# OECOC_controlbord.net
KiCad netlist of a schematic drawn in EAGLE
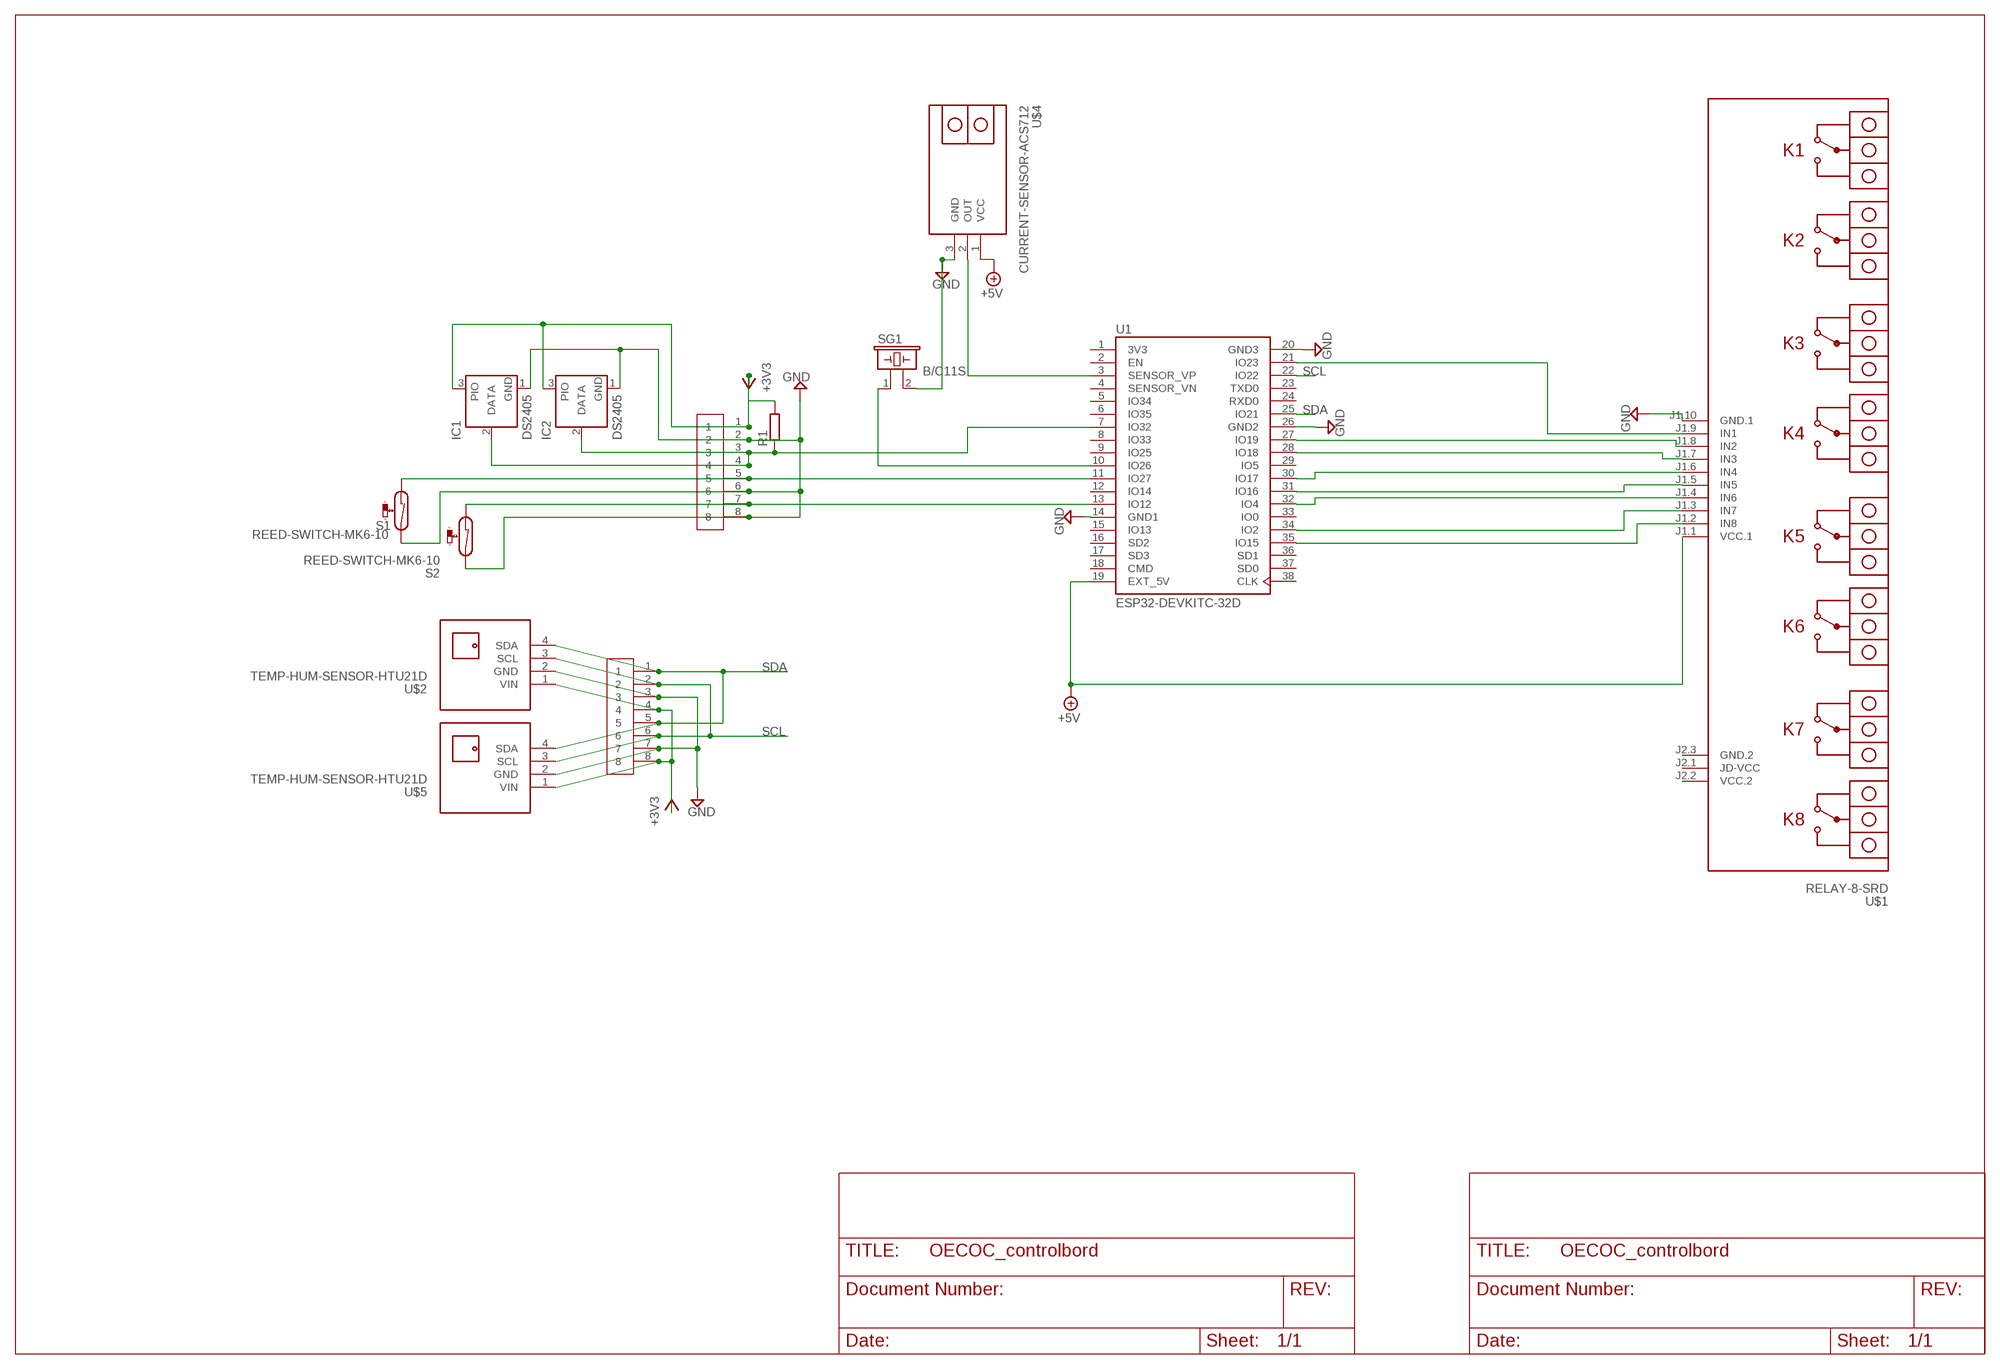
[diagram p0: schematic, sheet 1]

(export (version "E")
  (design (tool "Eeschema 10.0.6"))
  (components
    (comp (ref "IC1")
      (value "DS2405")
      (footprint "eagle-import:TO92-")
      (fields (field (name "MF") "DALLAS SEMICONDUCTOR"))
      (libsource (lib "eagle-import") (part "DS2405"))
    )
    (comp (ref "IC2")
      (value "DS2405")
      (footprint "eagle-import:TO92-")
      (fields (field (name "MF") "DALLAS SEMICONDUCTOR"))
      (libsource (lib "eagle-import") (part "DS2405"))
    )
    (comp (ref "R1")
      (value "R-EU_0207/10")
      (footprint "eagle-import:0207_10")
      (libsource (lib "eagle-import") (part "R-EU_0207/10"))
    )
    (comp (ref "S1")
      (value "REED-SWITCH-MK6-10")
      (footprint "eagle-import:MK6-10")
      (libsource (lib "eagle-import") (part "REED-SWITCH-MK6-10"))
    )
    (comp (ref "S2")
      (value "REED-SWITCH-MK6-10")
      (footprint "eagle-import:MK6-10")
      (libsource (lib "eagle-import") (part "REED-SWITCH-MK6-10"))
    )
    (comp (ref "SG1")
      (value "B/C11S")
      (footprint "eagle-import:B_C11S")
      (libsource (lib "eagle-import") (part "B/C11S"))
    )
    (comp (ref "U$1")
      (value "RELAY-8-SRD")
      (footprint "eagle-import:RELAY-8-SRD")
      (libsource (lib "eagle-import") (part "RELAY-8-SRD"))
    )
    (comp (ref "U$2")
      (value "TEMP-HUM-SENSOR-HTU21D")
      (footprint "eagle-import:TEMP-HUM-SENSOR-HTU21D")
      (libsource (lib "eagle-import") (part "TEMP-HUM-SENSOR-HTU21D"))
    )
    (comp (ref "U$3")
      (value "PHOENIXCONTACT_PINSTRIP")
      (footprint "eagle-import:HDRV8W150P500_1X8_2488X140X1204B")
      (libsource (lib "eagle-import") (part "PHOENIXCONTACT_PINSTRIP"))
    )
    (comp (ref "U$4")
      (value "CURRENT-SENSOR-ACS712")
      (footprint "eagle-import:CURRENT-SENSOR-ACS712")
      (libsource (lib "eagle-import") (part "CURRENT-SENSOR-ACS712"))
    )
    (comp (ref "U$5")
      (value "TEMP-HUM-SENSOR-HTU21D")
      (footprint "eagle-import:TEMP-HUM-SENSOR-HTU21D")
      (libsource (lib "eagle-import") (part "TEMP-HUM-SENSOR-HTU21D"))
    )
    (comp (ref "U$6")
      (value "PHOENIXCONTACT_PINSTRIP")
      (footprint "eagle-import:HDRV8W150P500_1X8_2488X140X1204B")
      (libsource (lib "eagle-import") (part "PHOENIXCONTACT_PINSTRIP"))
    )
    (comp (ref "U1")
      (value "ESP32-DEVKITC-32D")
      (footprint "eagle-import:MODULE_ESP32-DEVKITC-32D")
      (fields (field (name "MF") "Espressif Systems"))
      (libsource (lib "eagle-import") (part "ESP32-DEVKITC-32D"))
    )
  )
  (nets
    (net (code "1") (name "+3V3") (class "Default")
      (node (ref "IC1") (pin "3") (pinfunction "PIO_3") (pintype "passive"))
      (node (ref "IC2") (pin "3") (pinfunction "PIO_3") (pintype "passive"))
      (node (ref "R1") (pin "2") (pinfunction "2_2") (pintype "passive"))
      (node (ref "U$2") (pin "1") (pinfunction "VIN_1") (pintype "power_in"))
      (node (ref "U$3") (pin "4") (pinfunction "4_4") (pintype "bidirectional"))
      (node (ref "U$3") (pin "8") (pinfunction "8_8") (pintype "bidirectional"))
      (node (ref "U$5") (pin "1") (pinfunction "VIN_1") (pintype "power_in"))
      (node (ref "U$6") (pin "1") (pinfunction "1_1") (pintype "bidirectional"))
    )
    (net (code "2") (name "+5V") (class "Default")
      (node (ref "U$1") (pin "J1.1") (pinfunction "VCC.1_J1.1") (pintype "power_in"))
      (node (ref "U$4") (pin "1") (pinfunction "VCC_1") (pintype "power_in"))
      (node (ref "U1") (pin "19") (pinfunction "EXT_5V_19") (pintype "power_in"))
    )
    (net (code "3") (name "/3V3") (class "Default")
      (node (ref "U1") (pin "1") (pinfunction "3V3_1") (pintype "power_in"))
    )
    (net (code "4") (name "/GND.2") (class "Default")
      (node (ref "U$1") (pin "J2.3") (pinfunction "GND.2_J2.3") (pintype "power_in"))
    )
    (net (code "5") (name "/SCL") (class "Default")
      (node (ref "U$2") (pin "3") (pinfunction "SCL_3") (pintype "bidirectional"))
      (node (ref "U$3") (pin "2") (pinfunction "2_2") (pintype "bidirectional"))
      (node (ref "U$3") (pin "6") (pinfunction "6_6") (pintype "bidirectional"))
      (node (ref "U$5") (pin "3") (pinfunction "SCL_3") (pintype "bidirectional"))
      (node (ref "U1") (pin "22") (pinfunction "IO22_22") (pintype "bidirectional"))
    )
    (net (code "6") (name "/SDA") (class "Default")
      (node (ref "U$2") (pin "4") (pinfunction "SDA_4") (pintype "bidirectional"))
      (node (ref "U$3") (pin "1") (pinfunction "1_1") (pintype "bidirectional"))
      (node (ref "U$3") (pin "5") (pinfunction "5_5") (pintype "bidirectional"))
      (node (ref "U$5") (pin "4") (pinfunction "SDA_4") (pintype "bidirectional"))
      (node (ref "U1") (pin "25") (pinfunction "IO21_25") (pintype "bidirectional"))
    )
    (net (code "7") (name "/VCC.2") (class "Default")
      (node (ref "U$1") (pin "J2.2") (pinfunction "VCC.2_J2.2") (pintype "power_in"))
    )
    (net (code "8") (name "GND") (class "Default")
      (node (ref "IC1") (pin "1") (pinfunction "GND_1") (pintype "passive"))
      (node (ref "IC2") (pin "1") (pinfunction "GND_1") (pintype "passive"))
      (node (ref "S1") (pin "2") (pinfunction "2_2") (pintype "passive"))
      (node (ref "S2") (pin "2") (pinfunction "2_2") (pintype "passive"))
      (node (ref "SG1") (pin "2") (pinfunction "2_2") (pintype "passive"))
      (node (ref "U$1") (pin "J1.10") (pinfunction "GND.1_J1.10") (pintype "power_in"))
      (node (ref "U$2") (pin "2") (pinfunction "GND_2") (pintype "power_in"))
      (node (ref "U$3") (pin "3") (pinfunction "3_3") (pintype "bidirectional"))
      (node (ref "U$3") (pin "7") (pinfunction "7_7") (pintype "bidirectional"))
      (node (ref "U$4") (pin "3") (pinfunction "GND_3") (pintype "power_in"))
      (node (ref "U$5") (pin "2") (pinfunction "GND_2") (pintype "power_in"))
      (node (ref "U$6") (pin "2") (pinfunction "2_2") (pintype "bidirectional"))
      (node (ref "U$6") (pin "6") (pinfunction "6_6") (pintype "bidirectional"))
      (node (ref "U$6") (pin "8") (pinfunction "8_8") (pintype "bidirectional"))
      (node (ref "U1") (pin "14") (pinfunction "GND1_14") (pintype "power_in"))
      (node (ref "U1") (pin "20") (pinfunction "GND3_20") (pintype "power_in"))
      (node (ref "U1") (pin "26") (pinfunction "GND2_26") (pintype "power_in"))
    )
    (net (code "9") (name "Net-(IC1-DATA)") (class "Default")
      (node (ref "IC1") (pin "2") (pinfunction "DATA_2") (pintype "input"))
      (node (ref "IC2") (pin "2") (pinfunction "DATA_2") (pintype "input"))
      (node (ref "R1") (pin "1") (pinfunction "1_1") (pintype "passive"))
      (node (ref "U$6") (pin "3") (pinfunction "3_3") (pintype "bidirectional"))
      (node (ref "U$6") (pin "4") (pinfunction "4_4") (pintype "bidirectional"))
      (node (ref "U1") (pin "7") (pinfunction "IO32_7") (pintype "bidirectional"))
    )
    (net (code "10") (name "Net-(U$1-IN1)") (class "Default")
      (node (ref "U$1") (pin "J1.9") (pinfunction "IN1_J1.9") (pintype "bidirectional"))
      (node (ref "U1") (pin "21") (pinfunction "IO23_21") (pintype "bidirectional"))
    )
    (net (code "11") (name "Net-(U$1-IN2)") (class "Default")
      (node (ref "U$1") (pin "J1.8") (pinfunction "IN2_J1.8") (pintype "bidirectional"))
      (node (ref "U1") (pin "27") (pinfunction "IO19_27") (pintype "bidirectional"))
    )
    (net (code "12") (name "Net-(U$1-IN3)") (class "Default")
      (node (ref "U$1") (pin "J1.7") (pinfunction "IN3_J1.7") (pintype "bidirectional"))
      (node (ref "U1") (pin "28") (pinfunction "IO18_28") (pintype "bidirectional"))
    )
    (net (code "13") (name "Net-(U$1-IN4)") (class "Default")
      (node (ref "U$1") (pin "J1.6") (pinfunction "IN4_J1.6") (pintype "bidirectional"))
      (node (ref "U1") (pin "30") (pinfunction "IO17_30") (pintype "bidirectional"))
    )
    (net (code "14") (name "Net-(U$1-IN5)") (class "Default")
      (node (ref "U$1") (pin "J1.5") (pinfunction "IN5_J1.5") (pintype "bidirectional"))
      (node (ref "U1") (pin "31") (pinfunction "IO16_31") (pintype "bidirectional"))
    )
    (net (code "15") (name "Net-(U$1-IN6)") (class "Default")
      (node (ref "U$1") (pin "J1.4") (pinfunction "IN6_J1.4") (pintype "bidirectional"))
      (node (ref "U1") (pin "32") (pinfunction "IO4_32") (pintype "bidirectional"))
    )
    (net (code "16") (name "Net-(U$1-IN7)") (class "Default")
      (node (ref "U$1") (pin "J1.3") (pinfunction "IN7_J1.3") (pintype "bidirectional"))
      (node (ref "U1") (pin "34") (pinfunction "IO2_34") (pintype "bidirectional"))
    )
    (net (code "17") (name "Net-(U$1-IN8)") (class "Default")
      (node (ref "U$1") (pin "J1.2") (pinfunction "IN8_J1.2") (pintype "bidirectional"))
      (node (ref "U1") (pin "35") (pinfunction "IO15_35") (pintype "bidirectional"))
    )
    (net (code "18") (name "Net-(U$4-OUT)") (class "Default")
      (node (ref "U$4") (pin "2") (pinfunction "OUT_2") (pintype "output"))
      (node (ref "U1") (pin "3") (pinfunction "SENSOR_VP_3") (pintype "input"))
    )
    (net (code "19") (name "Net-(U1-IO12)") (class "Default")
      (node (ref "S2") (pin "1") (pinfunction "1_1") (pintype "passive"))
      (node (ref "U$6") (pin "7") (pinfunction "7_7") (pintype "bidirectional"))
      (node (ref "U1") (pin "13") (pinfunction "IO12_13") (pintype "bidirectional"))
    )
    (net (code "20") (name "Net-(U1-IO26)") (class "Default")
      (node (ref "SG1") (pin "1") (pinfunction "1_1") (pintype "passive"))
      (node (ref "U1") (pin "10") (pinfunction "IO26_10") (pintype "bidirectional"))
    )
    (net (code "21") (name "Net-(U1-IO27)") (class "Default")
      (node (ref "S1") (pin "1") (pinfunction "1_1") (pintype "passive"))
      (node (ref "U$6") (pin "5") (pinfunction "5_5") (pintype "bidirectional"))
      (node (ref "U1") (pin "11") (pinfunction "IO27_11") (pintype "bidirectional"))
    )
    (net (code "22") (name "unconnected-(U$1-JD-VCC-PadJ2.1)") (class "Default")
      (node (ref "U$1") (pin "J2.1") (pinfunction "JD-VCC_J2.1") (pintype "bidirectional"))
    )
    (net (code "23") (name "unconnected-(U1-CLK-Pad38)") (class "Default")
      (node (ref "U1") (pin "38") (pinfunction "CLK_38") (pintype "input"))
    )
    (net (code "24") (name "unconnected-(U1-CMD-Pad18)") (class "Default")
      (node (ref "U1") (pin "18") (pinfunction "CMD_18") (pintype "bidirectional"))
    )
    (net (code "25") (name "unconnected-(U1-EN-Pad2)") (class "Default")
      (node (ref "U1") (pin "2") (pinfunction "EN_2") (pintype "input"))
    )
    (net (code "26") (name "unconnected-(U1-IO0-Pad33)") (class "Default")
      (node (ref "U1") (pin "33") (pinfunction "IO0_33") (pintype "bidirectional"))
    )
    (net (code "27") (name "unconnected-(U1-IO5-Pad29)") (class "Default")
      (node (ref "U1") (pin "29") (pinfunction "IO5_29") (pintype "bidirectional"))
    )
    (net (code "28") (name "unconnected-(U1-IO13-Pad15)") (class "Default")
      (node (ref "U1") (pin "15") (pinfunction "IO13_15") (pintype "bidirectional"))
    )
    (net (code "29") (name "unconnected-(U1-IO14-Pad12)") (class "Default")
      (node (ref "U1") (pin "12") (pinfunction "IO14_12") (pintype "bidirectional"))
    )
    (net (code "30") (name "unconnected-(U1-IO25-Pad9)") (class "Default")
      (node (ref "U1") (pin "9") (pinfunction "IO25_9") (pintype "bidirectional"))
    )
    (net (code "31") (name "unconnected-(U1-IO33-Pad8)") (class "Default")
      (node (ref "U1") (pin "8") (pinfunction "IO33_8") (pintype "bidirectional"))
    )
    (net (code "32") (name "unconnected-(U1-IO34-Pad5)") (class "Default")
      (node (ref "U1") (pin "5") (pinfunction "IO34_5") (pintype "bidirectional"))
    )
    (net (code "33") (name "unconnected-(U1-IO35-Pad6)") (class "Default")
      (node (ref "U1") (pin "6") (pinfunction "IO35_6") (pintype "bidirectional"))
    )
    (net (code "34") (name "unconnected-(U1-RXD0-Pad24)") (class "Default")
      (node (ref "U1") (pin "24") (pinfunction "RXD0_24") (pintype "input"))
    )
    (net (code "35") (name "unconnected-(U1-SD0-Pad37)") (class "Default")
      (node (ref "U1") (pin "37") (pinfunction "SD0_37") (pintype "bidirectional"))
    )
    (net (code "36") (name "unconnected-(U1-SD1-Pad36)") (class "Default")
      (node (ref "U1") (pin "36") (pinfunction "SD1_36") (pintype "bidirectional"))
    )
    (net (code "37") (name "unconnected-(U1-SD2-Pad16)") (class "Default")
      (node (ref "U1") (pin "16") (pinfunction "SD2_16") (pintype "bidirectional"))
    )
    (net (code "38") (name "unconnected-(U1-SD3-Pad17)") (class "Default")
      (node (ref "U1") (pin "17") (pinfunction "SD3_17") (pintype "bidirectional"))
    )
    (net (code "39") (name "unconnected-(U1-SENSOR_VN-Pad4)") (class "Default")
      (node (ref "U1") (pin "4") (pinfunction "SENSOR_VN_4") (pintype "input"))
    )
    (net (code "40") (name "unconnected-(U1-TXD0-Pad23)") (class "Default")
      (node (ref "U1") (pin "23") (pinfunction "TXD0_23") (pintype "output"))
    )
  )
)
